# Sheet.net
KiCad netlist of a schematic drawn in Altium Designer
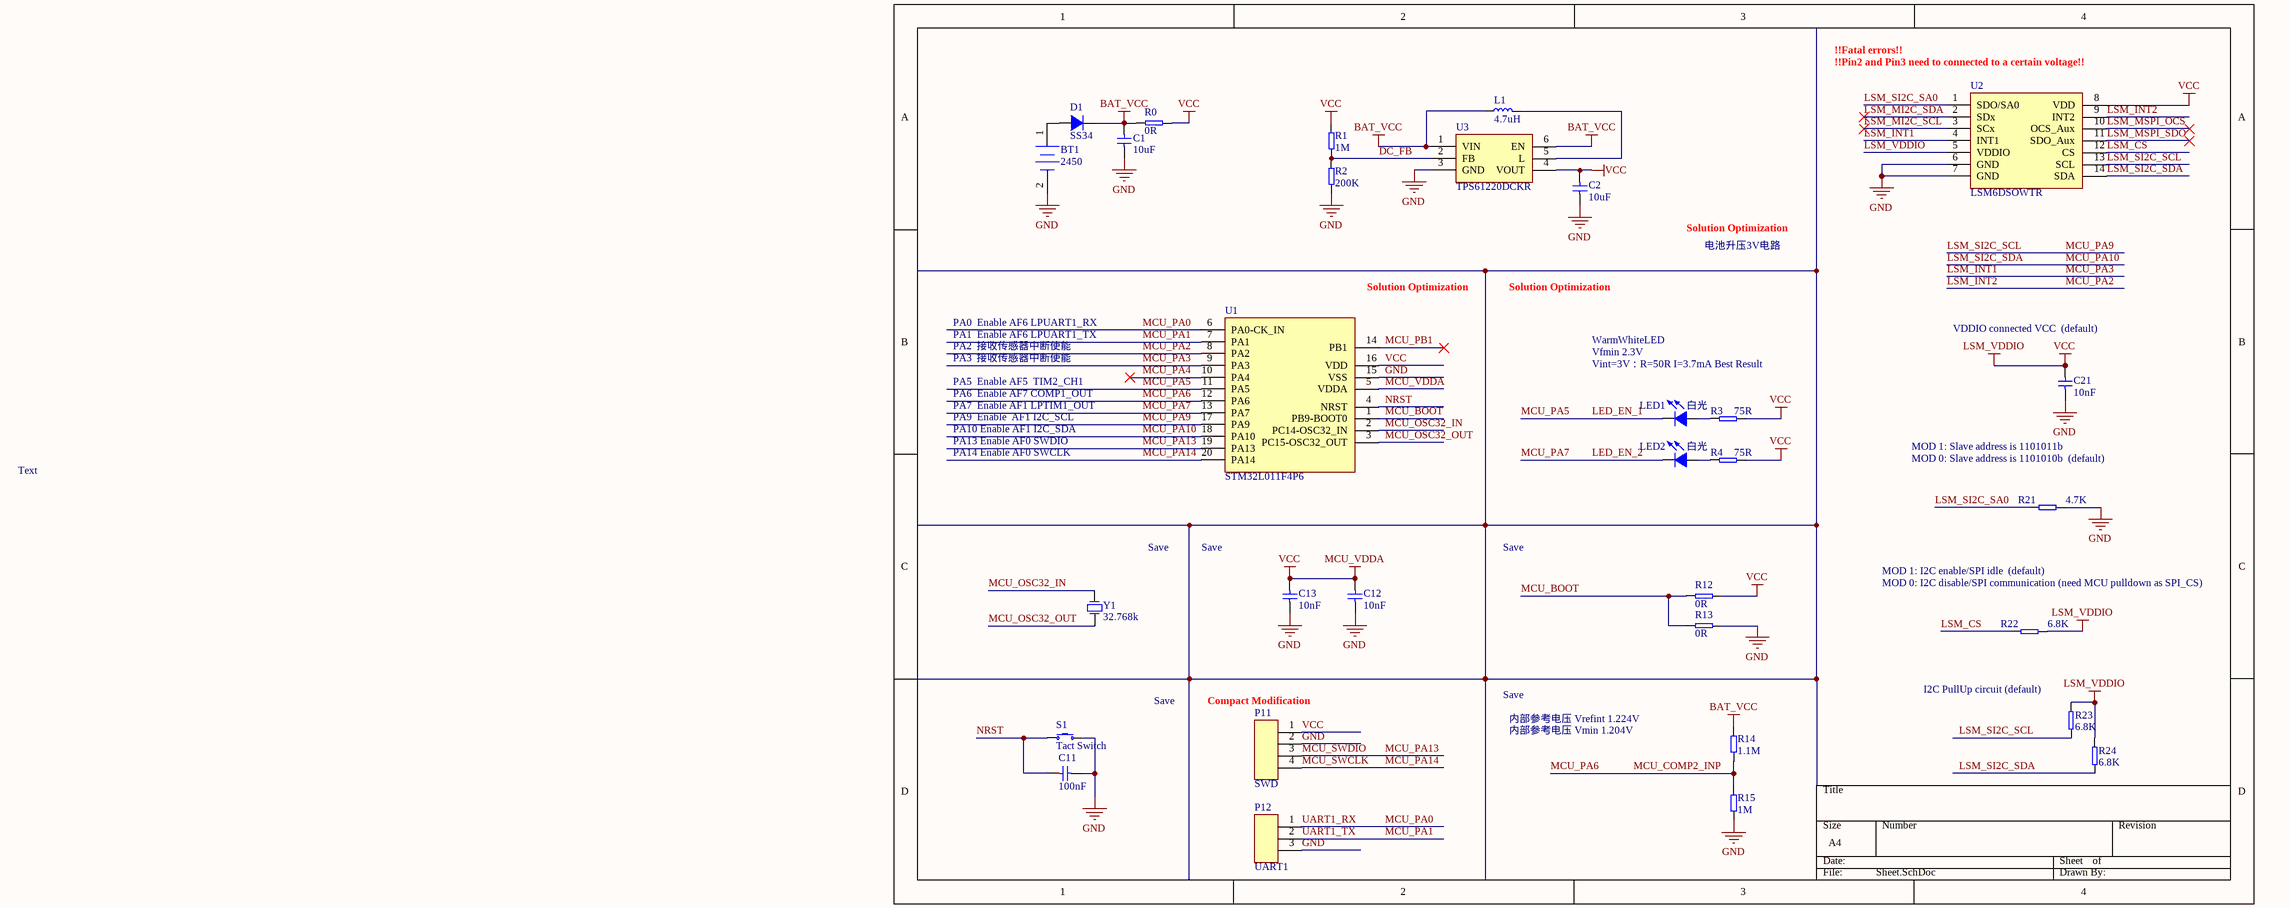
[diagram p0: Sheet.SchDoc]

(export (version "E")
  (design (tool "Eeschema 10.0.6"))
  (components
    (comp (ref "BT1")
      (value "2450")
      (footprint "CR2450_CJ")
      (description "Multicell Battery")
      (fields (field (name "PUBLISHER") "Altium Limited"))
      (libsource (lib "Miscellaneous Devices") (part "Battery"))
    )
    (comp (ref "C1") (value "10uF") (footprint "0603-C") (libsource (lib "Schlib1") (part "Cap")))
    (comp (ref "C2") (value "10uF") (footprint "0603-C") (libsource (lib "Schlib1") (part "Cap")))
    (comp (ref "C11") (value "100nF") (footprint "0603-C") (libsource (lib "Schlib1") (part "Cap")))
    (comp (ref "C12") (value "10nF") (footprint "0603-C") (libsource (lib "Schlib1") (part "Cap")))
    (comp (ref "C13") (value "10nF") (footprint "0603-C") (libsource (lib "Schlib1") (part "Cap")))
    (comp (ref "C21") (value "10nF") (footprint "0603-C") (libsource (lib "Schlib1") (part "Cap")))
    (comp (ref "D1") (value "SS34") (footprint "SOD-123") (libsource (lib "Schlib1") (part "Diode")))
    (comp (ref "L1") (value "4.7uH") (footprint "0805-L") (libsource (lib "Schlib1") (part "Inductor")))
    (comp (ref "LED1") (value "白光") (footprint "0805-LED") (libsource (lib "Schlib1") (part "LED")))
    (comp (ref "LED2") (value "白光") (footprint "0805-LED") (libsource (lib "Schlib1") (part "LED")))
    (comp (ref "P11")
      (value "SWD")
      (footprint "2.54mm 1x4P")
      (libsource (lib "Schlib1") (part "Header 1x4P"))
    )
    (comp (ref "P12")
      (value "UART1")
      (footprint "2.54mm 1x3P")
      (libsource (lib "Schlib1") (part "Header 1x3P"))
    )
    (comp (ref "R0") (value "0R") (footprint "0603-R") (libsource (lib "Schlib1") (part "Res")))
    (comp (ref "R1") (value "1M") (footprint "0603-R") (libsource (lib "Schlib1") (part "Res")))
    (comp (ref "R2") (value "200K") (footprint "0603-R") (libsource (lib "Schlib1") (part "Res")))
    (comp (ref "R3") (value "75R") (footprint "0603-R") (libsource (lib "Schlib1") (part "Res")))
    (comp (ref "R4") (value "75R") (footprint "0603-R") (libsource (lib "Schlib1") (part "Res")))
    (comp (ref "R12") (value "0R") (footprint "0603-R") (libsource (lib "Schlib1") (part "Res")))
    (comp (ref "R13") (value "0R") (footprint "0603-R") (libsource (lib "Schlib1") (part "Res")))
    (comp (ref "R14") (value "1.1M") (footprint "0603-R") (libsource (lib "Schlib1") (part "Res")))
    (comp (ref "R15") (value "1M") (footprint "0603-R") (libsource (lib "Schlib1") (part "Res")))
    (comp (ref "R21") (value "4.7K") (footprint "0603-R") (libsource (lib "Schlib1") (part "Res")))
    (comp (ref "R22") (value "6.8K") (footprint "0603-R") (libsource (lib "Schlib1") (part "Res")))
    (comp (ref "R23") (value "6.8K") (footprint "0603-R") (libsource (lib "Schlib1") (part "Res")))
    (comp (ref "R24") (value "6.8K") (footprint "0603-R") (libsource (lib "Schlib1") (part "Res")))
    (comp (ref "S1")
      (value "Tact Switch")
      (footprint "TS-3025")
      (libsource (lib "Schlib1") (part "Tact Switch"))
    )
    (comp (ref "U1")
      (value "STM32L011F4P6")
      (footprint "TSSOP-20")
      (libsource (lib "Schlib1") (part "STM32L011F4P6"))
    )
    (comp (ref "U2")
      (value "LSM6DSOWTR")
      (footprint "LGA-14L(2.5x3.0)")
      (description "6-axis IMU (inertial measurement unit): \r\nalways-on 3‑axis accelerometer and 3‑axis gyroscop")
      (libsource (lib "Schlib1") (part "LSM6DSOWTR"))
    )
    (comp (ref "U3")
      (value "TPS61220DCKR")
      (footprint "SC-70-6")
      (description "TPS6122x Low Input Voltage, 0.7V Boost Converter With 5.5μA Quiescent Current")
      (libsource (lib "Schlib1") (part "TPS61220DCKR"))
    )
    (comp (ref "Y1") (value "32.768k") (footprint "SMD3215-2P") (libsource (lib "Schlib1") (part "XTAL")))
  )
  (nets
    (net (code "1") (name "/DC_FB") (class "Default")
      (node (ref "R1") (pin "1") (pinfunction "1_1") (pintype "passive"))
      (node (ref "R2") (pin "2") (pinfunction "2_2") (pintype "passive"))
      (node (ref "U3") (pin "2") (pinfunction "FB_2") (pintype "passive"))
    )
    (net (code "2") (name "/LED_EN_1") (class "Default")
      (node (ref "LED1") (pin "1") (pinfunction "1_1") (pintype "passive"))
      (node (ref "U1") (pin "11") (pinfunction "PA5_11") (pintype "passive"))
    )
    (net (code "3") (name "/LED_EN_2") (class "Default")
      (node (ref "LED2") (pin "1") (pinfunction "1_1") (pintype "passive"))
      (node (ref "U1") (pin "13") (pinfunction "PA7_13") (pintype "passive"))
    )
    (net (code "4") (name "/LSM_CS") (class "Default")
      (node (ref "R22") (pin "1") (pinfunction "1_1") (pintype "passive"))
      (node (ref "U2") (pin "12") (pinfunction "CS_12") (pintype "passive"))
    )
    (net (code "5") (name "/LSM_INT1") (class "Default")
      (node (ref "U1") (pin "9") (pinfunction "PA3_9") (pintype "passive"))
      (node (ref "U2") (pin "4") (pinfunction "INT1_4") (pintype "passive"))
    )
    (net (code "6") (name "/LSM_INT2") (class "Default")
      (node (ref "U1") (pin "8") (pinfunction "PA2_8") (pintype "passive"))
      (node (ref "U2") (pin "9") (pinfunction "INT2_9") (pintype "passive"))
    )
    (net (code "7") (name "/LSM_MI2C_SCL") (class "Default")
      (node (ref "U2") (pin "3") (pinfunction "SCx_3") (pintype "passive+no_connect"))
    )
    (net (code "8") (name "/LSM_MI2C_SDA") (class "Default")
      (node (ref "U2") (pin "2") (pinfunction "SDx_2") (pintype "passive+no_connect"))
    )
    (net (code "9") (name "/LSM_MSPI_OCS") (class "Default")
      (node (ref "U2") (pin "10") (pinfunction "OCS_Aux_10") (pintype "passive+no_connect"))
    )
    (net (code "10") (name "/LSM_MSPI_SDO") (class "Default")
      (node (ref "U2") (pin "11") (pinfunction "SDO_Aux_11") (pintype "passive+no_connect"))
    )
    (net (code "11") (name "/LSM_SI2C_SA0") (class "Default")
      (node (ref "R21") (pin "1") (pinfunction "1_1") (pintype "passive"))
      (node (ref "U2") (pin "1") (pinfunction "SDO/SA0_1") (pintype "passive"))
    )
    (net (code "12") (name "/LSM_SI2C_SCL") (class "Default")
      (node (ref "R23") (pin "1") (pinfunction "1_1") (pintype "passive"))
      (node (ref "U1") (pin "17") (pinfunction "PA9_17") (pintype "passive"))
      (node (ref "U2") (pin "13") (pinfunction "SCL_13") (pintype "passive"))
    )
    (net (code "13") (name "/LSM_SI2C_SDA") (class "Default")
      (node (ref "R24") (pin "1") (pinfunction "1_1") (pintype "passive"))
      (node (ref "U1") (pin "18") (pinfunction "PA10_18") (pintype "passive"))
      (node (ref "U2") (pin "14") (pinfunction "SDA_14") (pintype "passive"))
    )
    (net (code "14") (name "/MCU_BOOT") (class "Default")
      (node (ref "R12") (pin "2") (pinfunction "2_2") (pintype "passive"))
      (node (ref "R13") (pin "2") (pinfunction "2_2") (pintype "passive"))
      (node (ref "U1") (pin "1") (pinfunction "PB9-BOOT0_1") (pintype "passive"))
    )
    (net (code "15") (name "/MCU_COMP2_INP") (class "Default")
      (node (ref "R14") (pin "1") (pinfunction "1_1") (pintype "passive"))
      (node (ref "R15") (pin "2") (pinfunction "2_2") (pintype "passive"))
      (node (ref "U1") (pin "12") (pinfunction "PA6_12") (pintype "passive"))
    )
    (net (code "16") (name "/MCU_OSC32_IN") (class "Default")
      (node (ref "U1") (pin "2") (pinfunction "PC14-OSC32_IN_2") (pintype "passive"))
      (node (ref "Y1") (pin "2") (pinfunction "2_2") (pintype "passive"))
    )
    (net (code "17") (name "/MCU_OSC32_OUT") (class "Default")
      (node (ref "U1") (pin "3") (pinfunction "PC15-OSC32_OUT_3") (pintype "passive"))
      (node (ref "Y1") (pin "1") (pinfunction "1_1") (pintype "passive"))
    )
    (net (code "18") (name "/MCU_PA0") (class "Default")
      (node (ref "P12") (pin "1") (pinfunction "1_1") (pintype "passive"))
      (node (ref "U1") (pin "6") (pinfunction "PA0-CK_IN_6") (pintype "passive"))
    )
    (net (code "19") (name "/MCU_PA1") (class "Default")
      (node (ref "P12") (pin "2") (pinfunction "2_2") (pintype "passive"))
      (node (ref "U1") (pin "7") (pinfunction "PA1_7") (pintype "passive"))
    )
    (net (code "20") (name "/MCU_PA4") (class "Default")
      (node (ref "U1") (pin "10") (pinfunction "PA4_10") (pintype "passive+no_connect"))
    )
    (net (code "21") (name "/MCU_PA13") (class "Default")
      (node (ref "P11") (pin "3") (pinfunction "3_3") (pintype "passive"))
      (node (ref "U1") (pin "19") (pinfunction "PA13_19") (pintype "passive"))
    )
    (net (code "22") (name "/MCU_PA14") (class "Default")
      (node (ref "P11") (pin "4") (pinfunction "4_4") (pintype "passive"))
      (node (ref "U1") (pin "20") (pinfunction "PA14_20") (pintype "passive"))
    )
    (net (code "23") (name "/MCU_PB1") (class "Default")
      (node (ref "U1") (pin "14") (pinfunction "PB1_14") (pintype "passive+no_connect"))
    )
    (net (code "24") (name "/NRST") (class "Default")
      (node (ref "C11") (pin "1") (pinfunction "1_1") (pintype "passive"))
      (node (ref "S1") (pin "1") (pinfunction "1_1") (pintype "passive"))
      (node (ref "U1") (pin "4") (pinfunction "NRST_4") (pintype "passive"))
    )
    (net (code "25") (name "BAT_VCC") (class "Default")
      (node (ref "C1") (pin "2") (pinfunction "2_2") (pintype "passive"))
      (node (ref "D1") (pin "1") (pinfunction "1_1") (pintype "passive"))
      (node (ref "L1") (pin "1") (pinfunction "1_1") (pintype "passive"))
      (node (ref "R0") (pin "2") (pinfunction "2_2") (pintype "passive"))
      (node (ref "R14") (pin "2") (pinfunction "2_2") (pintype "passive"))
      (node (ref "U3") (pin "1") (pinfunction "VIN_1") (pintype "passive"))
      (node (ref "U3") (pin "6") (pinfunction "EN_6") (pintype "passive"))
    )
    (net (code "26") (name "GND") (class "Default")
      (node (ref "BT1") (pin "2") (pinfunction "-_2") (pintype "passive"))
      (node (ref "C1") (pin "1") (pinfunction "1_1") (pintype "passive"))
      (node (ref "C11") (pin "2") (pinfunction "2_2") (pintype "passive"))
      (node (ref "C12") (pin "1") (pinfunction "1_1") (pintype "passive"))
      (node (ref "C13") (pin "1") (pinfunction "1_1") (pintype "passive"))
      (node (ref "C2") (pin "1") (pinfunction "1_1") (pintype "passive"))
      (node (ref "C21") (pin "1") (pinfunction "1_1") (pintype "passive"))
      (node (ref "P11") (pin "2") (pinfunction "2_2") (pintype "passive"))
      (node (ref "P12") (pin "3") (pinfunction "3_3") (pintype "passive"))
      (node (ref "R13") (pin "1") (pinfunction "1_1") (pintype "passive"))
      (node (ref "R15") (pin "1") (pinfunction "1_1") (pintype "passive"))
      (node (ref "R2") (pin "1") (pinfunction "1_1") (pintype "passive"))
      (node (ref "R21") (pin "2") (pinfunction "2_2") (pintype "passive"))
      (node (ref "S1") (pin "2") (pinfunction "2_2") (pintype "passive"))
      (node (ref "U1") (pin "15") (pinfunction "VSS_15") (pintype "passive"))
      (node (ref "U2") (pin "6") (pinfunction "GND_6") (pintype "passive"))
      (node (ref "U2") (pin "7") (pinfunction "GND_7") (pintype "passive"))
      (node (ref "U3") (pin "3") (pinfunction "GND_3") (pintype "passive"))
    )
    (net (code "27") (name "LSM_VDDIO") (class "Default")
      (node (ref "C12") (pin "2") (pinfunction "2_2") (pintype "passive"))
      (node (ref "C13") (pin "2") (pinfunction "2_2") (pintype "passive"))
      (node (ref "C2") (pin "2") (pinfunction "2_2") (pintype "passive"))
      (node (ref "C21") (pin "2") (pinfunction "2_2") (pintype "passive"))
      (node (ref "P11") (pin "1") (pinfunction "1_1") (pintype "passive"))
      (node (ref "R0") (pin "1") (pinfunction "1_1") (pintype "passive"))
      (node (ref "R1") (pin "2") (pinfunction "2_2") (pintype "passive"))
      (node (ref "R12") (pin "1") (pinfunction "1_1") (pintype "passive"))
      (node (ref "R22") (pin "2") (pinfunction "2_2") (pintype "passive"))
      (node (ref "R23") (pin "2") (pinfunction "2_2") (pintype "passive"))
      (node (ref "R24") (pin "2") (pinfunction "2_2") (pintype "passive"))
      (node (ref "R3") (pin "2") (pinfunction "2_2") (pintype "passive"))
      (node (ref "R4") (pin "2") (pinfunction "2_2") (pintype "passive"))
      (node (ref "U1") (pin "16") (pinfunction "VDD_16") (pintype "passive"))
      (node (ref "U1") (pin "5") (pinfunction "VDDA_5") (pintype "passive"))
      (node (ref "U2") (pin "5") (pinfunction "VDDIO_5") (pintype "passive"))
      (node (ref "U2") (pin "8") (pinfunction "VDD_8") (pintype "passive"))
      (node (ref "U3") (pin "4") (pinfunction "VOUT_4") (pintype "passive"))
    )
    (net (code "28") (name "Net-(BT1-+)") (class "Default")
      (node (ref "BT1") (pin "1") (pinfunction "+_1") (pintype "passive"))
      (node (ref "D1") (pin "2") (pinfunction "2_2") (pintype "passive"))
    )
    (net (code "29") (name "Net-(LED1-Pad2)") (class "Default")
      (node (ref "LED1") (pin "2") (pinfunction "2_2") (pintype "passive"))
      (node (ref "R3") (pin "1") (pinfunction "1_1") (pintype "passive"))
    )
    (net (code "30") (name "Net-(LED2-Pad2)") (class "Default")
      (node (ref "LED2") (pin "2") (pinfunction "2_2") (pintype "passive"))
      (node (ref "R4") (pin "1") (pinfunction "1_1") (pintype "passive"))
    )
    (net (code "31") (name "Net-(U3-L)") (class "Default")
      (node (ref "L1") (pin "2") (pinfunction "2_2") (pintype "passive"))
      (node (ref "U3") (pin "5") (pinfunction "L_5") (pintype "passive"))
    )
  )
)
